# main-board.net
KiCad netlist of a schematic drawn in Altium Designer
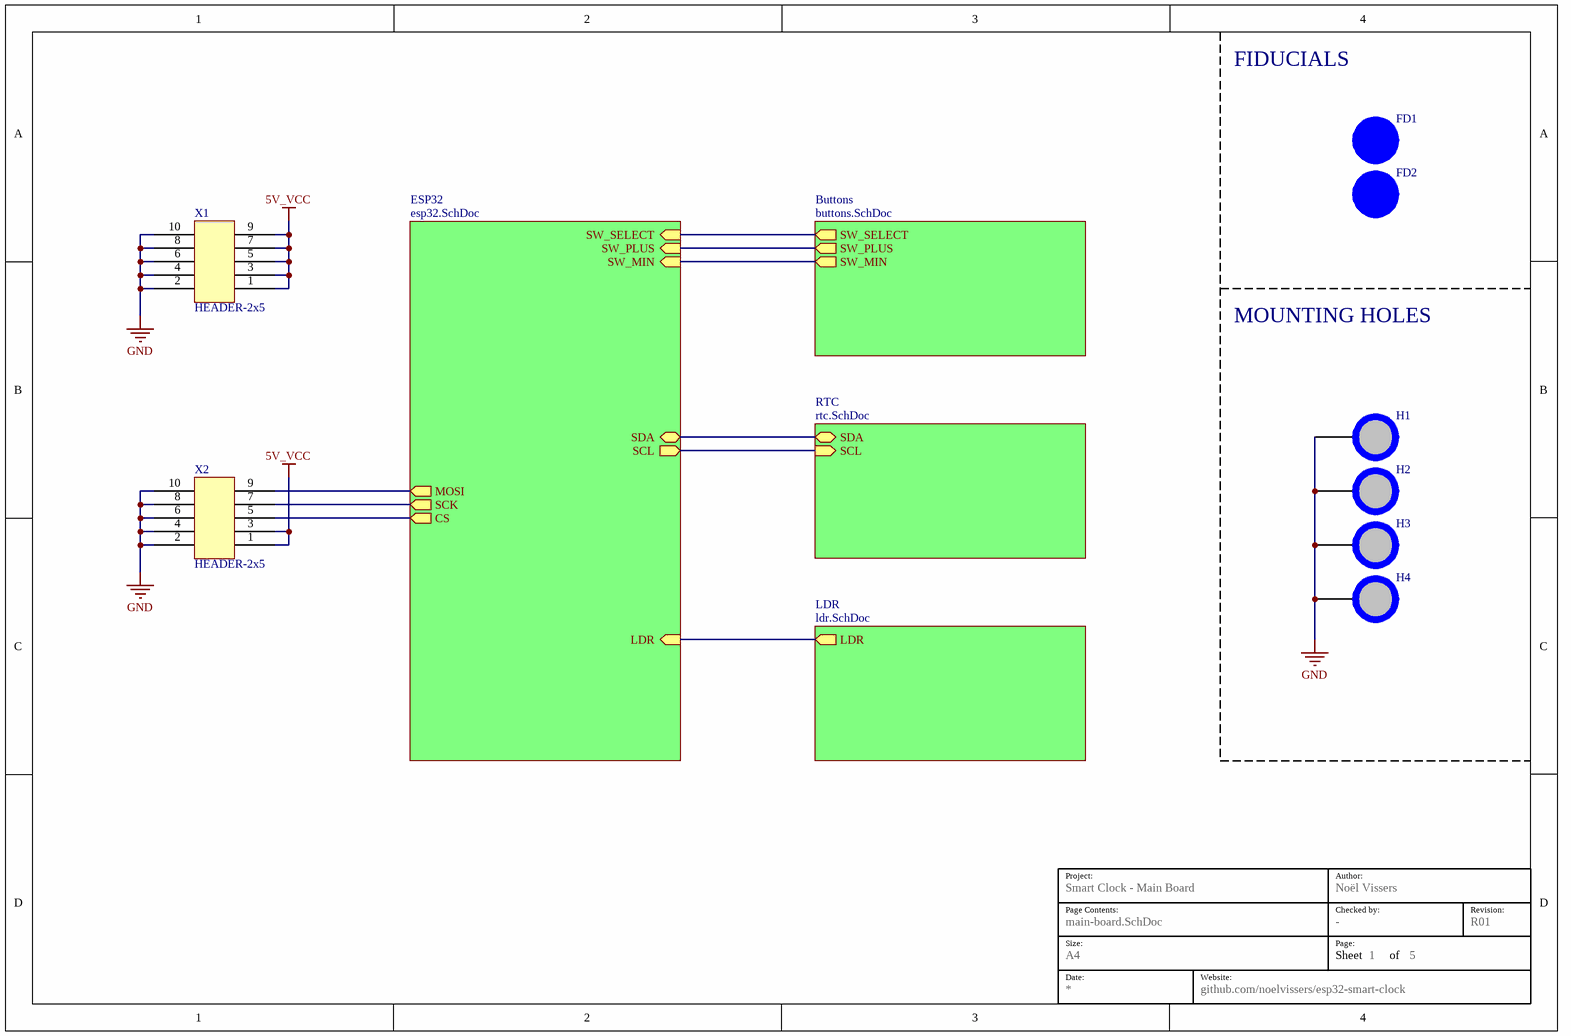
[diagram p0: main-board.SchDoc]

(export (version "E")
  (design (tool "Eeschema 10.0.6"))
  (components
    (comp (ref "*")
      (value "TITLE BLOCK")
      (fields (field (name "SIZE") "A4"))
      (libsource (lib "smart-clock-lib") (part "TITLE BLOCK"))
    )
    (comp (ref "FD1")
      (value "FD")
      (footprint "FD")
      (description "FIDUCIAL MARKER")
      (libsource (lib "smart-clock-lib") (part "FD"))
    )
    (comp (ref "FD2")
      (value "FD")
      (footprint "FD")
      (description "FIDUCIAL MARKER")
      (libsource (lib "smart-clock-lib") (part "FD"))
    )
    (comp (ref "H1")
      (value "SIZE")
      (footprint "HOLE")
      (description "M3 MOUNTING HOLE WITH SCREW AND SPACER")
      (libsource (lib "smart-clock-lib") (part "MOUNTING-HOLE"))
    )
    (comp (ref "H2")
      (value "SIZE")
      (footprint "HOLE")
      (description "M3 MOUNTING HOLE WITH SCREW AND SPACER")
      (libsource (lib "smart-clock-lib") (part "MOUNTING-HOLE"))
    )
    (comp (ref "H3")
      (value "SIZE")
      (footprint "HOLE")
      (description "M3 MOUNTING HOLE WITH SCREW AND SPACER")
      (libsource (lib "smart-clock-lib") (part "MOUNTING-HOLE"))
    )
    (comp (ref "H4")
      (value "SIZE")
      (footprint "HOLE")
      (description "M3 MOUNTING HOLE WITH SCREW AND SPACER")
      (libsource (lib "smart-clock-lib") (part "MOUNTING-HOLE"))
    )
    (comp (ref "X1")
      (value "HEADER-2x5")
      (footprint "HEADER-2x5-FEMALE")
      (description "2.54mm HEADER 2x5")
      (libsource (lib "smart-clock-lib") (part "HEADER-2x5"))
    )
    (comp (ref "X2")
      (value "HEADER-2x5")
      (footprint "HEADER-2x5-FEMALE")
      (description "2.54mm HEADER 2x5")
      (libsource (lib "smart-clock-lib") (part "HEADER-2x5"))
    )
  )
  (nets
    (net (code "1") (name "/CS") (class "Default")
      (node (ref "X2") (pin "5") (pinfunction "5_5") (pintype "passive"))
    )
    (net (code "3") (name "/MOSI") (class "Default")
      (node (ref "X2") (pin "9") (pinfunction "9_9") (pintype "passive"))
    )
    (net (code "4") (name "/SCK") (class "Default")
      (node (ref "X2") (pin "7") (pinfunction "7_7") (pintype "passive"))
    )
    (net (code "10") (name "5V_VCC") (class "Default")
      (node (ref "X1") (pin "1") (pinfunction "1_1") (pintype "passive"))
      (node (ref "X1") (pin "3") (pinfunction "3_3") (pintype "passive"))
      (node (ref "X1") (pin "5") (pinfunction "5_5") (pintype "passive"))
      (node (ref "X1") (pin "7") (pinfunction "7_7") (pintype "passive"))
      (node (ref "X1") (pin "9") (pinfunction "9_9") (pintype "passive"))
      (node (ref "X2") (pin "1") (pinfunction "1_1") (pintype "passive"))
      (node (ref "X2") (pin "3") (pinfunction "3_3") (pintype "passive"))
    )
    (net (code "11") (name "GND") (class "Default")
      (node (ref "H1") (pin "1") (pintype "passive"))
      (node (ref "H2") (pin "1") (pintype "passive"))
      (node (ref "H3") (pin "1") (pintype "passive"))
      (node (ref "H4") (pin "1") (pintype "passive"))
      (node (ref "X1") (pin "10") (pinfunction "10_10") (pintype "passive"))
      (node (ref "X1") (pin "2") (pinfunction "2_2") (pintype "passive"))
      (node (ref "X1") (pin "4") (pinfunction "4_4") (pintype "passive"))
      (node (ref "X1") (pin "6") (pinfunction "6_6") (pintype "passive"))
      (node (ref "X1") (pin "8") (pinfunction "8_8") (pintype "passive"))
      (node (ref "X2") (pin "10") (pinfunction "10_10") (pintype "passive"))
      (node (ref "X2") (pin "2") (pinfunction "2_2") (pintype "passive"))
      (node (ref "X2") (pin "4") (pinfunction "4_4") (pintype "passive"))
      (node (ref "X2") (pin "6") (pinfunction "6_6") (pintype "passive"))
      (node (ref "X2") (pin "8") (pinfunction "8_8") (pintype "passive"))
    )
    (net (code "12") (name "unconnected-(FD1-Pad1)") (class "Default")
      (node (ref "FD1") (pin "1") (pinfunction "1_1") (pintype "passive"))
    )
    (net (code "13") (name "unconnected-(FD2-Pad1)") (class "Default")
      (node (ref "FD2") (pin "1") (pinfunction "1_1") (pintype "passive"))
    )
  )
)
